# Schematics.net
KiCad netlist of a schematic drawn in Altium Designer
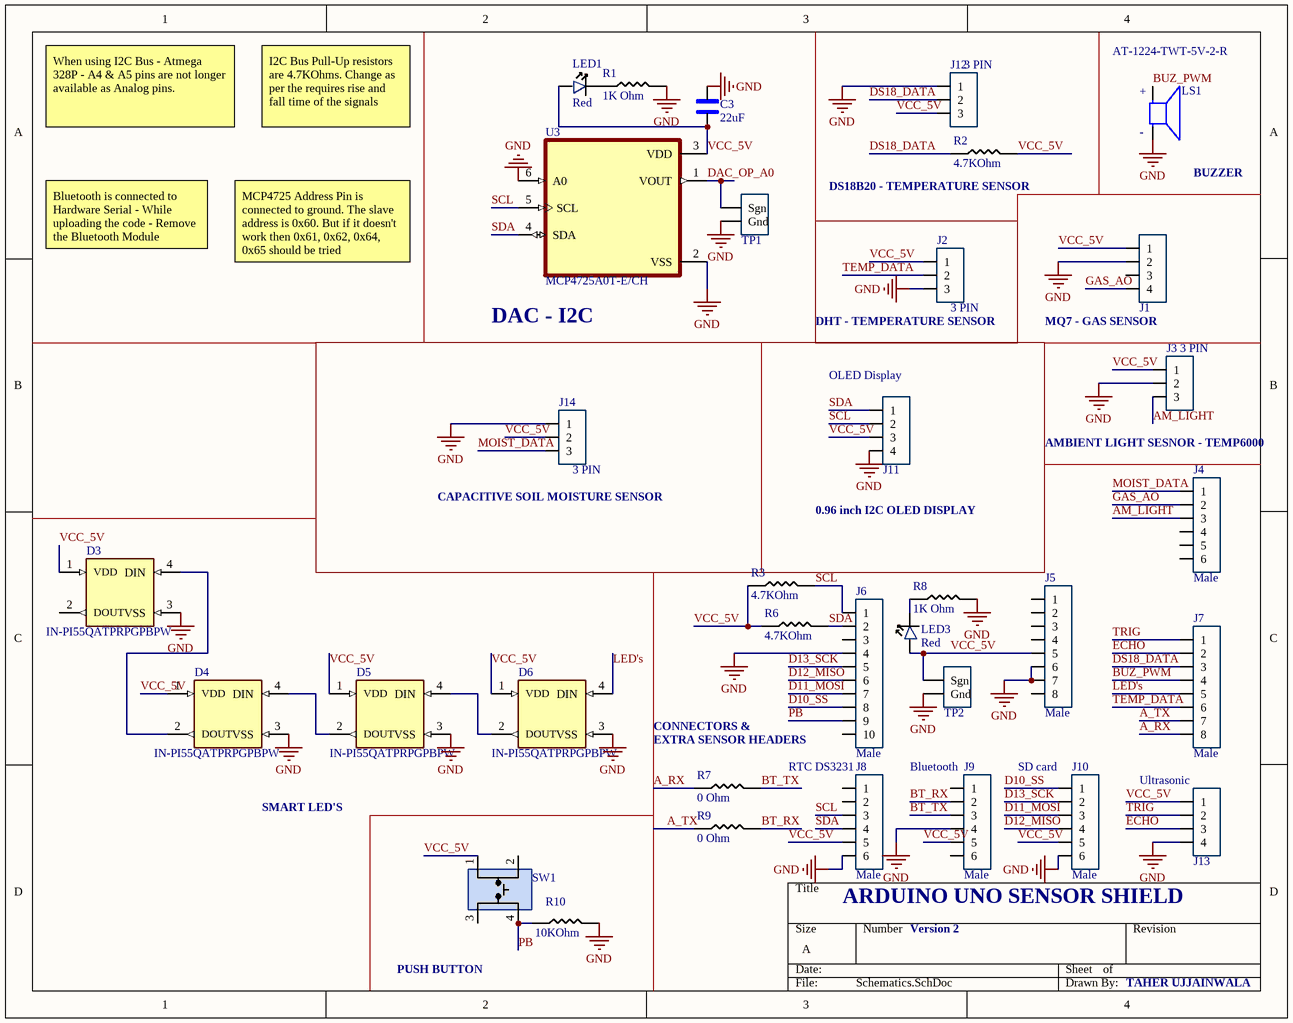
[diagram p0: Schematics.SchDoc]

(export (version "E")
  (design (tool "Eeschema 10.0.6"))
  (components
    (comp (ref "C3")
      (value "22uF")
      (footprint "1206_Passive_Capacitor")
      (description "22µF ±20% 16V Ceramic Capacitor X5R 1206 (3216 Metric)")
      (fields (field (name "DIGIKEY PART") "1276-2728-1-ND") (field (name "LCSC PART#") "C12891"))
      (libsource (lib "ECEN5730Lib_Manual_2021_08") (part "C_22uF_1206"))
    )
    (comp (ref "D3")
      (value "IN-PI55QATPRPGPBPW")
      (footprint "SERIAL_LED")
      (description "Digital Series Cascade LED")
      (libsource (lib "ECEN5730Lib_Manual_2021_08") (part "LED_Smart_5050"))
    )
    (comp (ref "D4")
      (value "IN-PI55QATPRPGPBPW")
      (footprint "SERIAL_LED")
      (description "Digital Series Cascade LED")
      (libsource (lib "ECEN5730Lib_Manual_2021_08") (part "LED_Smart_5050"))
    )
    (comp (ref "D5")
      (value "IN-PI55QATPRPGPBPW")
      (footprint "SERIAL_LED")
      (description "Digital Series Cascade LED")
      (libsource (lib "ECEN5730Lib_Manual_2021_08") (part "LED_Smart_5050"))
    )
    (comp (ref "D6")
      (value "IN-PI55QATPRPGPBPW")
      (footprint "SERIAL_LED")
      (description "Digital Series Cascade LED")
      (fields (field (name "LCSC PART#") "C2843785"))
      (libsource (lib "ECEN5730Lib_Manual_2021_08") (part "LED_Smart_5050"))
    )
    (comp (ref "J1")
      (value "J_4_PIN_HEADER")
      (footprint "4_PIN_100MIL")
      (description "4 Position Header Connector 0.100\" (2.54mm) Through Hole Tin")
      (libsource (lib "ECEN5730Lib_Manual_2021_08") (part "J_4_PIN_HEADER"))
    )
    (comp (ref "J2")
      (value "3 PIN")
      (footprint "3_PIN_100mil")
      (description "3 2.54mm Straight 1 Header，Breakaway Through Hole Pin Header & Female Header ROHS")
      (fields (field (name "LCSC PART#") "C49257"))
      (libsource (lib "ECEN5730Lib_JLC_2021_08") (part "J_3_PIN_HEADER"))
    )
    (comp (ref "J3")
      (value "3 PIN")
      (footprint "3_PIN_100mil")
      (description "3 2.54mm Straight 1 Header，Breakaway Through Hole Pin Header & Female Header ROHS")
      (fields (field (name "LCSC PART#") "C49257"))
      (libsource (lib "ECEN5730Lib_JLC_2021_08") (part "J_3_PIN_HEADER"))
    )
    (comp (ref "J4")
      (value "Male")
      (footprint "6_PIN_ARDUINO_100mil")
      (description "6 Position Header Connector 0.100\" (2.54mm) Through Hole Tin")
      (fields (field (name "DIGIKEY PART") "S7004-ND") (field (name "LCSC PART#") "DNP"))
      (libsource (lib "ECEN5730Lib_Manual_2021_08") (part "JM_6_PIN_MALE_ARDUINO"))
    )
    (comp (ref "J5")
      (value "Male")
      (footprint "8_PIN_ARDUINO_100MIL")
      (description "8 Position Header Connector 0.100\" (2.54mm) Through Hole Tin")
      (fields (field (name "DIGIKEY PART") "S7006-ND") (field (name "LCSC PART#") "DNP"))
      (libsource (lib "ECEN5730Lib_Manual_2021_08") (part "JM_8_PIN_MALE_ARDUINO"))
    )
    (comp (ref "J6")
      (value "Male")
      (footprint "10_PIN_ARDUINO_100MIL")
      (description "10 Position Header Connector 0.100\" (2.54mm) Through Hole Tin")
      (fields (field (name "DIGIKEY PART") "S7008-ND") (field (name "LCSC PART#") "DNP"))
      (libsource (lib "ECEN5730Lib_Manual_2021_08") (part "JM_10_PIN_MALE_ARDUINO"))
    )
    (comp (ref "J7")
      (value "Male")
      (footprint "8_PIN_ARDUINO_100MIL")
      (description "8 Position Header Connector 0.100\" (2.54mm) Through Hole Tin")
      (fields (field (name "DIGIKEY PART") "S7006-ND") (field (name "LCSC PART#") "DNP"))
      (libsource (lib "ECEN5730Lib_Manual_2021_08") (part "JM_8_PIN_MALE_ARDUINO"))
    )
    (comp (ref "J8")
      (value "Male")
      (footprint "6_PIN_ARDUINO_100mil")
      (description "6 Position Header Connector 0.100\" (2.54mm) Through Hole Tin")
      (fields (field (name "DIGIKEY PART") "S7004-ND") (field (name "LCSC PART#") "DNP"))
      (libsource (lib "ECEN5730Lib_Manual_2021_08") (part "JM_6_PIN_MALE_ARDUINO"))
    )
    (comp (ref "J9")
      (value "Male")
      (footprint "6_PIN_ARDUINO_100mil")
      (description "6 Position Header Connector 0.100\" (2.54mm) Through Hole Tin")
      (fields (field (name "DIGIKEY PART") "S7004-ND") (field (name "LCSC PART#") "DNP"))
      (libsource (lib "ECEN5730Lib_Manual_2021_08") (part "JM_6_PIN_MALE_ARDUINO"))
    )
    (comp (ref "J10")
      (value "Male")
      (footprint "6_PIN_ARDUINO_100mil")
      (description "6 Position Header Connector 0.100\" (2.54mm) Through Hole Tin")
      (fields (field (name "DIGIKEY PART") "S7004-ND") (field (name "LCSC PART#") "DNP"))
      (libsource (lib "ECEN5730Lib_Manual_2021_08") (part "JM_6_PIN_MALE_ARDUINO"))
    )
    (comp (ref "J11")
      (value "J_4_PIN_HEADER")
      (footprint "4_PIN_100MIL")
      (description "4 Position Header Connector 0.100\" (2.54mm) Through Hole Tin")
      (libsource (lib "ECEN5730Lib_Manual_2021_08") (part "J_4_PIN_HEADER"))
    )
    (comp (ref "J12")
      (value "3 PIN")
      (footprint "3_PIN_100mil")
      (description "3 2.54mm Straight 1 Header，Breakaway Through Hole Pin Header & Female Header ROHS")
      (fields (field (name "LCSC PART#") "C49257"))
      (libsource (lib "ECEN5730Lib_JLC_2021_08") (part "J_3_PIN_HEADER"))
    )
    (comp (ref "J13")
      (value "J_4_PIN_HEADER")
      (footprint "4_PIN_100MIL")
      (description "4 Position Header Connector 0.100\" (2.54mm) Through Hole Tin")
      (libsource (lib "ECEN5730Lib_Manual_2021_08") (part "J_4_PIN_HEADER"))
    )
    (comp (ref "J14")
      (value "3 PIN")
      (footprint "3_PIN_100mil")
      (description "3 2.54mm Straight 1 Header，Breakaway Through Hole Pin Header & Female Header ROHS")
      (fields (field (name "LCSC PART#") "C49257"))
      (libsource (lib "ECEN5730Lib_JLC_2021_08") (part "J_3_PIN_HEADER"))
    )
    (comp (ref "LED1")
      (value "Red")
      (footprint "LED")
      (description "Red 638nm LED Indication - Discrete 1.8V 1206 (3216 Metric)")
      (fields (field (name "DIGIKEY PART") "160-1167-1-ND") (field (name "LCSC PART#") "C93133"))
      (libsource (lib "ECEN5730Lib_Manual_2021_08") (part "LED_1206"))
    )
    (comp (ref "LED3")
      (value "Red")
      (footprint "LED")
      (description "Red 638nm LED Indication - Discrete 1.8V 1206 (3216 Metric)")
      (fields (field (name "DIGIKEY PART") "160-1167-1-ND") (field (name "LCSC PART#") "C93133"))
      (libsource (lib "ECEN5730Lib_Manual_2021_08") (part "LED_1206"))
    )
    (comp (ref "LS1")
      (value "AT-1224-TWT-5V-2-R")
      (footprint "XDCR_AT-1224-TWT-5V-2-R")
      (description "AUDIO TRANSDUCER 5 VP-P 87 DB 2400 HZ")
      (fields (field (name "MF") "PUI Audio,") (field (name "LCSC PART#") "C417411"))
      (libsource (lib "AT-1224-TWT-5V-2-R") (part "AT-1224-TWT-5V-2-R"))
    )
    (comp (ref "R1")
      (value "1K Ohm")
      (footprint "1206_Passive_Resitor")
      (description "1 kOhms ±1% 0.5W, 1/2W Chip Resistor 1206 (3216 Metric) Anti-Sulfur, Moisture Resistant Thin Film")
      (fields (field (name "DIGIKEY PART") "RNCP1206FTD1K00CT-ND") (field (name "LCSC PART#") "C4410"))
      (libsource (lib "ECEN5730Lib_Manual_2021_08") (part "R_1K_1206"))
    )
    (comp (ref "R2")
      (value "4.7KOhm")
      (footprint "1206_Passive_Resitor")
      (description "4.7kΩ ±1% 0.25W ±100ppm/℃ 1206 Chip Resistor - Surface Mount RoHS")
      (fields (field (name "LCSC PART#") "C17936") (field (name "MFR PART #") "1206W4F4701T5E"))
      (libsource (lib "ECEN5730Lib_2023_01_DS") (part "R_4.7k_1206"))
    )
    (comp (ref "R3")
      (value "4.7KOhm")
      (footprint "1206_Passive_Resitor")
      (description "4.7kΩ ±1% 0.25W ±100ppm/℃ 1206 Chip Resistor - Surface Mount RoHS")
      (fields (field (name "LCSC PART#") "C17936") (field (name "MFR PART #") "1206W4F4701T5E"))
      (libsource (lib "ECEN5730Lib_2023_01_DS") (part "R_4.7k_1206"))
    )
    (comp (ref "R6")
      (value "4.7KOhm")
      (footprint "1206_Passive_Resitor")
      (description "4.7kΩ ±1% 0.25W ±100ppm/℃ 1206 Chip Resistor - Surface Mount RoHS")
      (fields (field (name "LCSC PART#") "C17936") (field (name "MFR PART #") "1206W4F4701T5E"))
      (libsource (lib "ECEN5730Lib_2023_01_DS") (part "R_4.7k_1206"))
    )
    (comp (ref "R7")
      (value "0 Ohm")
      (footprint "0402_Passive_Resistor")
      (description "CHIP RESISTOR - SURFACE MOUNT 0OHMS ±1% 1/16W 0402 ROHS")
      (fields (field (name "MFR PART #") "0402WGF0000TCE") (field (name "LCSC PART#") "C17168"))
      (libsource (lib "ECEN5730Lib_2023_01_DS") (part "R_0Ohm_0402"))
    )
    (comp (ref "R8")
      (value "1K Ohm")
      (footprint "1206_Passive_Resitor")
      (description "1 kOhms ±1% 0.5W, 1/2W Chip Resistor 1206 (3216 Metric) Anti-Sulfur, Moisture Resistant Thin Film")
      (fields (field (name "DIGIKEY PART") "RNCP1206FTD1K00CT-ND") (field (name "LCSC PART#") "C4410"))
      (libsource (lib "ECEN5730Lib_Manual_2021_08") (part "R_1K_1206"))
    )
    (comp (ref "R9")
      (value "0 Ohm")
      (footprint "0402_Passive_Resistor")
      (description "CHIP RESISTOR - SURFACE MOUNT 0OHMS ±1% 1/16W 0402 ROHS")
      (fields (field (name "MFR PART #") "0402WGF0000TCE") (field (name "LCSC PART#") "C17168"))
      (libsource (lib "ECEN5730Lib_2023_01_DS") (part "R_0Ohm_0402"))
    )
    (comp (ref "R10")
      (value "10KOhm")
      (footprint "1206_Passive_Resitor")
      (description "10 kOhms ±5% 0.25W, 1/4W Chip Resistor 1206 (3216 Metric) Automotive AEC-Q200 Thick Film")
      (fields (field (name "DIGIKEY PART") "RMCF1206JT300RCT-ND") (field (name "LCSC PART#") "C17902"))
      (libsource (lib "ECEN5730Lib_JLC_2021_08") (part "R_10KOhm_1206"))
    )
    (comp (ref "SW1")
      (value "TL3305AF160QG")
      (footprint "Switch_JLC")
      (description "Tactile Switch SPST-NO Top Actuated Surface Mount")
      (fields (field (name "MFR PART #") "KH-4.5X4.5X4.3H-STM") (field (name "LCSC PART#") "C2837550"))
      (libsource (lib "ECEN5730Lib_2023_01_DS") (part "SW_Push_Button_JLC"))
    )
    (comp (ref "TP1")
      (value "10x Probe TP")
      (footprint "TP10x_Probe")
      (description "Test Point 300 mil centers")
      (libsource (lib "ECEN5730Lib_Manual_2021_08") (part "TP_10x_Probe"))
    )
    (comp (ref "TP2")
      (value "10x Probe TP")
      (footprint "TP10x_Probe")
      (description "Test Point 300 mil centers")
      (libsource (lib "ECEN5730Lib_Manual_2021_08") (part "TP_10x_Probe"))
    )
    (comp (ref "U3")
      (value "MCP4725A0T-E/CH")
      (footprint "SOT95P270X145-6N")
      (description "12 Bit Digital to Analog Converter 1 SOT-23-6")
      (fields (field (name "MF") "Microchip") (field (name "LCSC PART#") "C144198"))
      (libsource (lib "MCP4725A0T-E_CH") (part "MCP4725A0T-E/CH"))
    )
  )
  (nets
    (net (code "1") (name "/AM_LIGHT") (class "Default")
      (node (ref "J3") (pin "3") (pinfunction "3_3") (pintype "passive"))
      (node (ref "J4") (pin "3") (pinfunction "3_3") (pintype "passive"))
    )
    (net (code "2") (name "/A_RX") (class "Default")
      (node (ref "J7") (pin "8") (pinfunction "8_8") (pintype "passive"))
      (node (ref "R7") (pin "1") (pinfunction "1_1") (pintype "passive"))
    )
    (net (code "3") (name "/A_TX") (class "Default")
      (node (ref "J7") (pin "7") (pinfunction "7_7") (pintype "passive"))
      (node (ref "R9") (pin "1") (pinfunction "1_1") (pintype "passive"))
    )
    (net (code "4") (name "/BT_RX") (class "Default")
      (node (ref "J9") (pin "2") (pinfunction "2_2") (pintype "passive"))
      (node (ref "R9") (pin "2") (pinfunction "2_2") (pintype "passive"))
    )
    (net (code "5") (name "/BT_TX") (class "Default")
      (node (ref "J9") (pin "3") (pinfunction "3_3") (pintype "passive"))
      (node (ref "R7") (pin "2") (pinfunction "2_2") (pintype "passive"))
    )
    (net (code "6") (name "/BUZ_PWM") (class "Default")
      (node (ref "J7") (pin "4") (pinfunction "4_4") (pintype "passive"))
      (node (ref "LS1") (pin "P") (pinfunction "P_P") (pintype "passive"))
    )
    (net (code "7") (name "/D10_SS") (class "Default")
      (node (ref "J10") (pin "1") (pinfunction "1_1") (pintype "passive"))
      (node (ref "J6") (pin "8") (pinfunction "8_8") (pintype "passive"))
    )
    (net (code "8") (name "/D11_MOSI") (class "Default")
      (node (ref "J10") (pin "3") (pinfunction "3_3") (pintype "passive"))
      (node (ref "J6") (pin "7") (pinfunction "7_7") (pintype "passive"))
    )
    (net (code "9") (name "/D12_MISO") (class "Default")
      (node (ref "J10") (pin "4") (pinfunction "4_4") (pintype "passive"))
      (node (ref "J6") (pin "6") (pinfunction "6_6") (pintype "passive"))
    )
    (net (code "10") (name "/D13_SCK") (class "Default")
      (node (ref "J10") (pin "2") (pinfunction "2_2") (pintype "passive"))
      (node (ref "J6") (pin "5") (pinfunction "5_5") (pintype "passive"))
    )
    (net (code "11") (name "/DAC_OP_A0") (class "Default")
      (node (ref "TP1") (pin "1") (pinfunction "Sgn_1") (pintype "passive"))
      (node (ref "U3") (pin "1") (pinfunction "VOUT_1") (pintype "output"))
    )
    (net (code "12") (name "/DS18_DATA") (class "Default")
      (node (ref "J12") (pin "2") (pinfunction "2_2") (pintype "passive"))
      (node (ref "J7") (pin "3") (pinfunction "3_3") (pintype "passive"))
      (node (ref "R2") (pin "1") (pinfunction "1_1") (pintype "passive"))
    )
    (net (code "13") (name "/ECHO") (class "Default")
      (node (ref "J13") (pin "3") (pinfunction "3_3") (pintype "passive"))
      (node (ref "J7") (pin "2") (pinfunction "2_2") (pintype "passive"))
    )
    (net (code "14") (name "/GAS_AO") (class "Default")
      (node (ref "J1") (pin "4") (pinfunction "4_4") (pintype "passive"))
      (node (ref "J4") (pin "2") (pinfunction "2_2") (pintype "passive"))
    )
    (net (code "15") (name "/LED's") (class "Default")
      (node (ref "D6") (pin "4") (pinfunction "DIN_4") (pintype "input"))
      (node (ref "J7") (pin "5") (pinfunction "5_5") (pintype "passive"))
    )
    (net (code "16") (name "/MOIST_DATA") (class "Default")
      (node (ref "J14") (pin "3") (pinfunction "3_3") (pintype "passive"))
      (node (ref "J4") (pin "1") (pinfunction "1_1") (pintype "passive"))
    )
    (net (code "17") (name "/PB") (class "Default")
      (node (ref "J6") (pin "9") (pinfunction "9_9") (pintype "passive"))
      (node (ref "R10") (pin "1") (pinfunction "1_1") (pintype "passive"))
      (node (ref "SW1") (pin "4") (pinfunction "4_4") (pintype "passive"))
    )
    (net (code "18") (name "/SCL") (class "Default")
      (node (ref "J11") (pin "2") (pinfunction "2_2") (pintype "passive"))
      (node (ref "J6") (pin "1") (pinfunction "1_1") (pintype "passive"))
      (node (ref "J8") (pin "3") (pinfunction "3_3") (pintype "passive"))
      (node (ref "R3") (pin "2") (pinfunction "2_2") (pintype "passive"))
      (node (ref "U3") (pin "5") (pinfunction "SCL_5") (pintype "input"))
    )
    (net (code "19") (name "/SDA") (class "Default")
      (node (ref "J11") (pin "1") (pinfunction "1_1") (pintype "passive"))
      (node (ref "J6") (pin "2") (pinfunction "2_2") (pintype "passive"))
      (node (ref "J8") (pin "4") (pinfunction "4_4") (pintype "passive"))
      (node (ref "R6") (pin "2") (pinfunction "2_2") (pintype "passive"))
      (node (ref "U3") (pin "4") (pinfunction "SDA_4") (pintype "bidirectional"))
    )
    (net (code "20") (name "/TEMP_DATA") (class "Default")
      (node (ref "J2") (pin "2") (pinfunction "2_2") (pintype "passive"))
      (node (ref "J7") (pin "6") (pinfunction "6_6") (pintype "passive"))
    )
    (net (code "21") (name "/TRIG") (class "Default")
      (node (ref "J13") (pin "2") (pinfunction "2_2") (pintype "passive"))
      (node (ref "J7") (pin "1") (pinfunction "1_1") (pintype "passive"))
    )
    (net (code "22") (name "/VCC_5V") (class "Default")
      (node (ref "C3") (pin "1") (pinfunction "1_1") (pintype "passive"))
      (node (ref "D3") (pin "1") (pinfunction "VDD_1") (pintype "input"))
      (node (ref "D4") (pin "1") (pinfunction "VDD_1") (pintype "input"))
      (node (ref "D5") (pin "1") (pinfunction "VDD_1") (pintype "input"))
      (node (ref "D6") (pin "1") (pinfunction "VDD_1") (pintype "input"))
      (node (ref "J1") (pin "1") (pinfunction "1_1") (pintype "passive"))
      (node (ref "J10") (pin "5") (pinfunction "5_5") (pintype "passive"))
      (node (ref "J11") (pin "3") (pinfunction "3_3") (pintype "passive"))
      (node (ref "J12") (pin "3") (pinfunction "3_3") (pintype "passive"))
      (node (ref "J13") (pin "1") (pinfunction "1_1") (pintype "passive"))
      (node (ref "J14") (pin "2") (pinfunction "2_2") (pintype "passive"))
      (node (ref "J2") (pin "1") (pinfunction "1_1") (pintype "passive"))
      (node (ref "J3") (pin "1") (pinfunction "1_1") (pintype "passive"))
      (node (ref "J5") (pin "5") (pinfunction "5_5") (pintype "passive"))
      (node (ref "J8") (pin "5") (pinfunction "5_5") (pintype "passive"))
      (node (ref "J9") (pin "5") (pinfunction "5_5") (pintype "passive"))
      (node (ref "LED1") (pin "2") (pinfunction "2_2") (pintype "passive"))
      (node (ref "LED3") (pin "2") (pinfunction "2_2") (pintype "passive"))
      (node (ref "R2") (pin "2") (pinfunction "2_2") (pintype "passive"))
      (node (ref "R3") (pin "1") (pinfunction "1_1") (pintype "passive"))
      (node (ref "R6") (pin "1") (pinfunction "1_1") (pintype "passive"))
      (node (ref "SW1") (pin "1") (pinfunction "1_1") (pintype "passive"))
      (node (ref "TP2") (pin "1") (pinfunction "Sgn_1") (pintype "passive"))
      (node (ref "U3") (pin "3") (pinfunction "VDD_3") (pintype "power_in"))
    )
    (net (code "23") (name "GND") (class "Default")
      (node (ref "C3") (pin "2") (pinfunction "2_2") (pintype "passive"))
      (node (ref "D3") (pin "3") (pinfunction "VSS_3") (pintype "input"))
      (node (ref "D4") (pin "3") (pinfunction "VSS_3") (pintype "input"))
      (node (ref "D5") (pin "3") (pinfunction "VSS_3") (pintype "input"))
      (node (ref "D6") (pin "3") (pinfunction "VSS_3") (pintype "input"))
      (node (ref "J1") (pin "2") (pinfunction "2_2") (pintype "passive"))
      (node (ref "J10") (pin "6") (pinfunction "6_6") (pintype "passive"))
      (node (ref "J11") (pin "4") (pinfunction "4_4") (pintype "passive"))
      (node (ref "J12") (pin "1") (pinfunction "1_1") (pintype "passive"))
      (node (ref "J13") (pin "4") (pinfunction "4_4") (pintype "passive"))
      (node (ref "J14") (pin "1") (pinfunction "1_1") (pintype "passive"))
      (node (ref "J2") (pin "3") (pinfunction "3_3") (pintype "passive"))
      (node (ref "J3") (pin "2") (pinfunction "2_2") (pintype "passive"))
      (node (ref "J5") (pin "6") (pinfunction "6_6") (pintype "passive"))
      (node (ref "J5") (pin "7") (pinfunction "7_7") (pintype "passive"))
      (node (ref "J6") (pin "4") (pinfunction "4_4") (pintype "passive"))
      (node (ref "J8") (pin "6") (pinfunction "6_6") (pintype "passive"))
      (node (ref "J9") (pin "4") (pinfunction "4_4") (pintype "passive"))
      (node (ref "LS1") (pin "N") (pinfunction "N_N") (pintype "passive"))
      (node (ref "R1") (pin "2") (pinfunction "2_2") (pintype "passive"))
      (node (ref "R10") (pin "2") (pinfunction "2_2") (pintype "passive"))
      (node (ref "R8") (pin "2") (pinfunction "2_2") (pintype "passive"))
      (node (ref "TP1") (pin "2") (pinfunction "Gnd_2") (pintype "passive"))
      (node (ref "TP2") (pin "2") (pinfunction "Gnd_2") (pintype "passive"))
      (node (ref "U3") (pin "2") (pinfunction "VSS_2") (pintype "power_in"))
      (node (ref "U3") (pin "6") (pinfunction "A0_6") (pintype "input"))
    )
    (net (code "24") (name "Net-(D3-DIN)") (class "Default")
      (node (ref "D3") (pin "4") (pinfunction "DIN_4") (pintype "input"))
      (node (ref "D4") (pin "2") (pinfunction "DOUT_2") (pintype "output"))
    )
    (net (code "25") (name "Net-(D4-DIN)") (class "Default")
      (node (ref "D4") (pin "4") (pinfunction "DIN_4") (pintype "input"))
      (node (ref "D5") (pin "2") (pinfunction "DOUT_2") (pintype "output"))
    )
    (net (code "26") (name "Net-(D5-DIN)") (class "Default")
      (node (ref "D5") (pin "4") (pinfunction "DIN_4") (pintype "input"))
      (node (ref "D6") (pin "2") (pinfunction "DOUT_2") (pintype "output"))
    )
    (net (code "27") (name "Net-(LED1-Pad1)") (class "Default")
      (node (ref "LED1") (pin "1") (pinfunction "1_1") (pintype "passive"))
      (node (ref "R1") (pin "1") (pinfunction "1_1") (pintype "passive"))
    )
    (net (code "28") (name "Net-(LED3-Pad1)") (class "Default")
      (node (ref "LED3") (pin "1") (pinfunction "1_1") (pintype "passive"))
      (node (ref "R8") (pin "1") (pinfunction "1_1") (pintype "passive"))
    )
    (net (code "29") (name "unconnected-(D3-DOUT-Pad2)") (class "Default")
      (node (ref "D3") (pin "2") (pinfunction "DOUT_2") (pintype "output"))
    )
    (net (code "30") (name "unconnected-(J1-Pad3)") (class "Default")
      (node (ref "J1") (pin "3") (pinfunction "3_3") (pintype "passive"))
    )
    (net (code "31") (name "unconnected-(J4-Pad4)") (class "Default")
      (node (ref "J4") (pin "4") (pinfunction "4_4") (pintype "passive"))
    )
    (net (code "32") (name "unconnected-(J4-Pad5)") (class "Default")
      (node (ref "J4") (pin "5") (pinfunction "5_5") (pintype "passive"))
    )
    (net (code "33") (name "unconnected-(J4-Pad6)") (class "Default")
      (node (ref "J4") (pin "6") (pinfunction "6_6") (pintype "passive"))
    )
    (net (code "34") (name "unconnected-(J5-Pad1)") (class "Default")
      (node (ref "J5") (pin "1") (pinfunction "1_1") (pintype "passive"))
    )
    (net (code "35") (name "unconnected-(J5-Pad2)") (class "Default")
      (node (ref "J5") (pin "2") (pinfunction "2_2") (pintype "passive"))
    )
    (net (code "36") (name "unconnected-(J5-Pad3)") (class "Default")
      (node (ref "J5") (pin "3") (pinfunction "3_3") (pintype "passive"))
    )
    (net (code "37") (name "unconnected-(J5-Pad4)") (class "Default")
      (node (ref "J5") (pin "4") (pinfunction "4_4") (pintype "passive"))
    )
    (net (code "38") (name "unconnected-(J5-Pad8)") (class "Default")
      (node (ref "J5") (pin "8") (pinfunction "8_8") (pintype "passive"))
    )
    (net (code "39") (name "unconnected-(J6-Pad3)") (class "Default")
      (node (ref "J6") (pin "3") (pinfunction "3_3") (pintype "passive"))
    )
    (net (code "40") (name "unconnected-(J6-Pad10)") (class "Default")
      (node (ref "J6") (pin "10") (pinfunction "10_10") (pintype "passive"))
    )
    (net (code "41") (name "unconnected-(J8-Pad1)") (class "Default")
      (node (ref "J8") (pin "1") (pinfunction "1_1") (pintype "passive"))
    )
    (net (code "42") (name "unconnected-(J8-Pad2)") (class "Default")
      (node (ref "J8") (pin "2") (pinfunction "2_2") (pintype "passive"))
    )
    (net (code "43") (name "unconnected-(J9-Pad1)") (class "Default")
      (node (ref "J9") (pin "1") (pinfunction "1_1") (pintype "passive"))
    )
    (net (code "44") (name "unconnected-(J9-Pad6)") (class "Default")
      (node (ref "J9") (pin "6") (pinfunction "6_6") (pintype "passive"))
    )
    (net (code "45") (name "unconnected-(SW1-Pad2)") (class "Default")
      (node (ref "SW1") (pin "2") (pinfunction "2_2") (pintype "passive"))
    )
    (net (code "46") (name "unconnected-(SW1-Pad3)") (class "Default")
      (node (ref "SW1") (pin "3") (pinfunction "3_3") (pintype "passive"))
    )
  )
)
